# WX0_008_942DL.net
KiCad netlist of a schematic drawn in Altium Designer
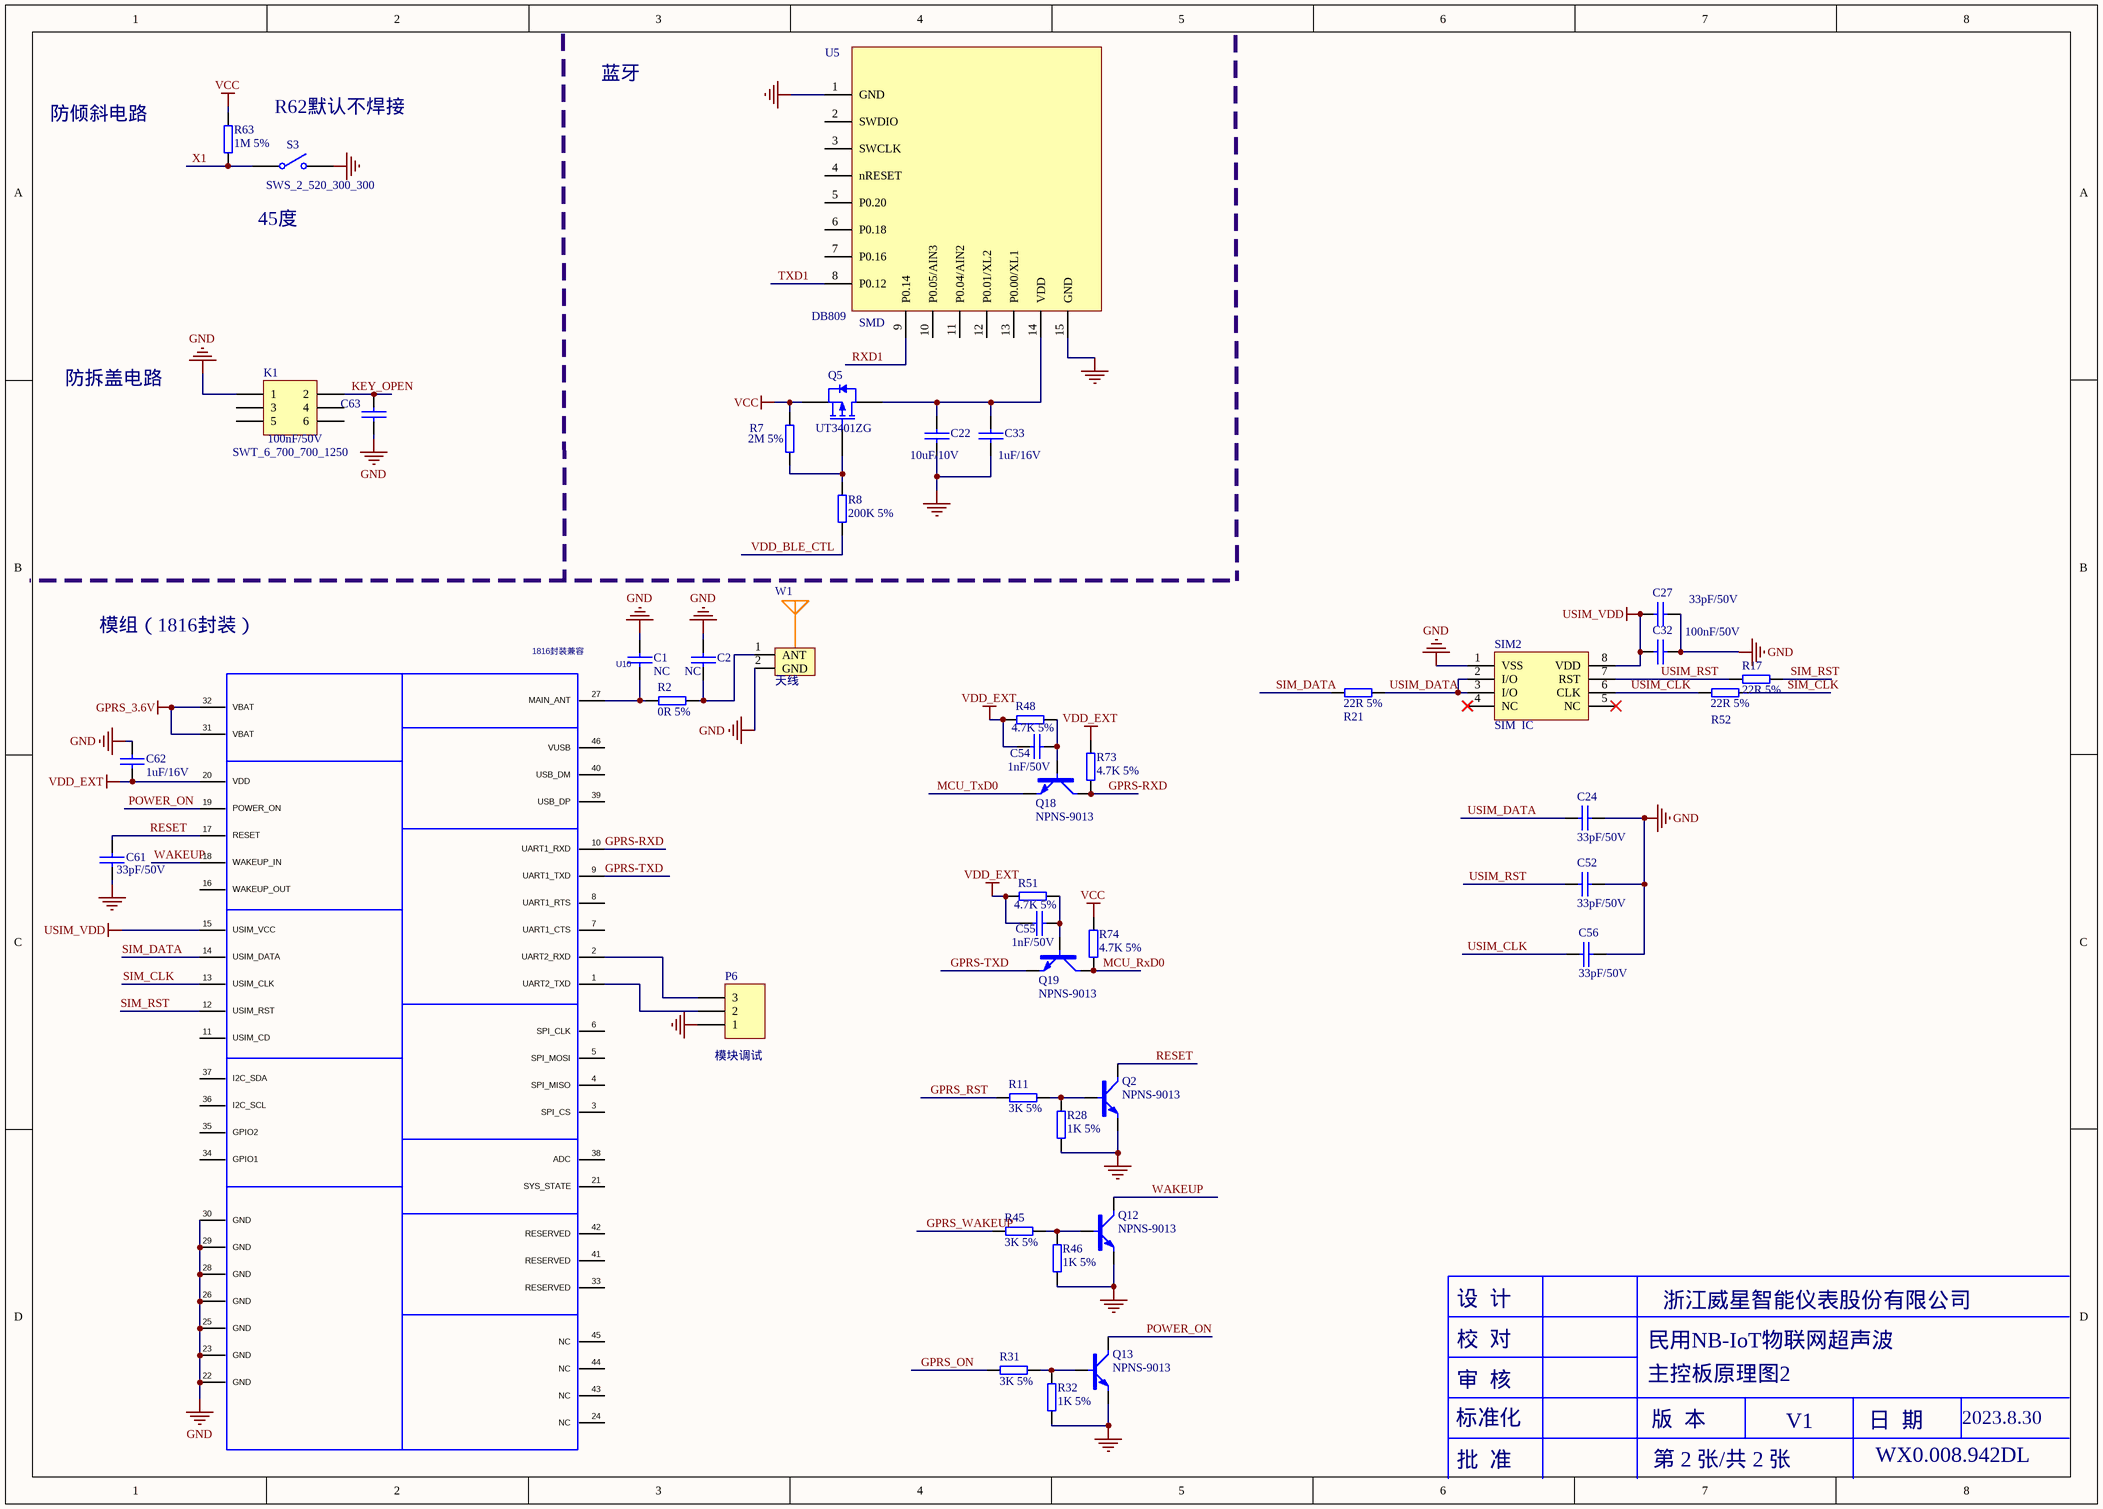
[diagram p0: WX0.008.942DL.SchDoc]

(export (version "E")
  (design (tool "Eeschema 10.0.6"))
  (components
    (comp (ref "C1")
      (value "NC")
      (footprint "CAP0603")
      (libsource (lib "Database_Libs2") (part "CC03JPO9_12P"))
    )
    (comp (ref "C2")
      (value "NC")
      (footprint "CAP0603")
      (libsource (lib "Database_Libs2") (part "CC03JPO9_12P"))
    )
    (comp (ref "C22")
      (value "10uF/10V")
      (footprint "CAP0603")
      (description "106pF,10 V,±10%,0603,村田,GRM188R61A106KE47D")
      (fields (field (name "PART NUMBER") "101020103-0026"))
      (libsource (lib "Database_Libs2") (part "CC03K5R6_10U"))
    )
    (comp (ref "C24")
      (value "33pF/50V")
      (footprint "CAP0603")
      (description "33pF,50 V,±10%,0603,国巨,CC0603KRNPO9BN33")
      (fields (field (name "PART NUMBER") "101020103-0027"))
      (libsource (lib "Database_Libs2") (part "CC03KPO9_33P"))
    )
    (comp (ref "C27")
      (value "33pF/50V")
      (footprint "CAP0603")
      (description "33pF,50 V,±10%,0603,国巨,CC0603KRNPO9BN33")
      (fields (field (name "PART NUMBER") "101020103-0027"))
      (libsource (lib "Database_Libs2") (part "CC03KPO9_33P"))
    )
    (comp (ref "C32")
      (value "100nF/50V")
      (footprint "CAP0603")
      (description "104pF,50 V,±10%,0603,国巨,CC0603KRX7R9BB104")
      (fields (field (name "PART NUMBER") "101020103-0021"))
      (libsource (lib "Database_Libs2") (part "CC03K7R9_100N"))
    )
    (comp (ref "C33")
      (value "1uF/16V")
      (footprint "CAP0603")
      (description "105pF,16 V,±10%,0603,国巨,CC0603KRX7R7BB105")
      (fields (field (name "PART NUMBER") "101020103-0003"))
      (libsource (lib "Database_Libs2") (part "CC03K7R7_1U"))
    )
    (comp (ref "C52")
      (value "33pF/50V")
      (footprint "CAP0603")
      (description "33pF,50 V,±10%,0603,国巨,CC0603KRNPO9BN33")
      (fields (field (name "PART NUMBER") "101020103-0027"))
      (libsource (lib "Database_Libs2") (part "CC03KPO9_33P"))
    )
    (comp (ref "C54")
      (value "1nF/50V")
      (footprint "CAP0603")
      (description "102pF,50 V,±10%,0603,国巨,CC0603KRX7R9BB102")
      (fields (field (name "PART NUMBER") "101020103-0022"))
      (libsource (lib "Database_Libs1") (part "CC03K7R9_1N"))
    )
    (comp (ref "C55")
      (value "1nF/50V")
      (footprint "CAP0603")
      (description "102pF,50 V,±10%,0603,国巨,CC0603KRX7R9BB102")
      (fields (field (name "PART NUMBER") "101020103-0022"))
      (libsource (lib "Database_Libs1") (part "CC03K7R9_1N"))
    )
    (comp (ref "C56")
      (value "33pF/50V")
      (footprint "CAP0603")
      (description "33pF,50 V,±10%,0603,国巨,CC0603KRNPO9BN33")
      (fields (field (name "PART NUMBER") "101020103-0027"))
      (libsource (lib "Database_Libs2") (part "CC03KPO9_33P"))
    )
    (comp (ref "C61")
      (value "33pF/50V")
      (footprint "CAP0603")
      (description "33pF,50 V,±10%,0603,国巨,CC0603KRNPO9BN33")
      (fields (field (name "PART NUMBER") "101020103-0027"))
      (libsource (lib "Database_Libs2") (part "CC03KPO9_33P"))
    )
    (comp (ref "C62")
      (value "1uF/16V")
      (footprint "CAP0603")
      (description "105pF,16 V,±10%,0603,国巨,CC0603KRX7R7BB105")
      (fields (field (name "PART NUMBER") "101020103-0003"))
      (libsource (lib "Database_Libs1") (part "CC03K7R7_1U"))
    )
    (comp (ref "C63")
      (value "100nF/50V")
      (footprint "CAP0603")
      (description "104pF,50 V,±10%,0603,国巨,CC0603KRX7R9BB104")
      (fields (field (name "PART NUMBER") "101020103-0021"))
      (libsource (lib "Database_Libs2") (part "CC03K7R9_100N"))
    )
    (comp (ref "K1")
      (value "SWT_6_700_700_1250")
      (footprint "KFT DIP-5.8X5.8")
      (description "7*7无锁按键,点触,7*7*12.5mm,7*7无锁按键,正立")
      (fields (field (name "PART NUMBER") "1011001-0037"))
      (libsource (lib "Database_Libs2") (part "07_SWT_6_700_700_1250"))
    )
    (comp (ref "P6")
      (value "模块调试")
      (footprint "PIN254_1*3*WXHJ")
      (description "1*3 ，Φ1.0 ，2.54mm，直脚,无需焊接器件")
      (fields (field (name "PART NUMBER") "AD_WXHJ_PinHeader_04"))
      (libsource (lib "Database_Libs2") (part "PIN254_1*3*WXHJ"))
    )
    (comp (ref "Q2")
      (value "NPNS-9013")
      (footprint "SOT-23")
      (description "9013,NPN,SOT-23,长电,S9013")
      (fields (field (name "PART NUMBER") "101040201-0002"))
      (libsource (lib "Database_Libs2") (part "03_NPNS-9013"))
    )
    (comp (ref "Q5")
      (value "UT3401ZG")
      (footprint "SOT-23")
      (description "UT3401ZG,P-MOS,SOT-23,UTC,UT3401ZG")
      (fields (field (name "PART NUMBER") "101040201-0013"))
      (libsource (lib "Database_Libs2") (part "03_P-UT3401ZG"))
    )
    (comp (ref "Q12")
      (value "NPNS-9013")
      (footprint "SOT-23")
      (description "9013,NPN,SOT-23,长电,S9013")
      (fields (field (name "PART NUMBER") "101040201-0002"))
      (libsource (lib "Database_Libs2") (part "03_NPNS-9013"))
    )
    (comp (ref "Q13")
      (value "NPNS-9013")
      (footprint "SOT-23")
      (description "9013,NPN,SOT-23,长电,S9013")
      (fields (field (name "PART NUMBER") "101040201-0002"))
      (libsource (lib "Database_Libs2") (part "03_NPNS-9013"))
    )
    (comp (ref "Q18")
      (value "NPNS-9013")
      (footprint "SOT-23")
      (description "9013,NPN,SOT-23,长电,S9013")
      (fields (field (name "PART NUMBER") "101040201-0002"))
      (libsource (lib "Database_Libs1") (part "03_NPNS-9013"))
    )
    (comp (ref "Q19")
      (value "NPNS-9013")
      (footprint "SOT-23")
      (description "9013,NPN,SOT-23,长电,S9013")
      (fields (field (name "PART NUMBER") "101040201-0002"))
      (libsource (lib "Database_Libs1") (part "03_NPNS-9013"))
    )
    (comp (ref "R2")
      (value "0R 5%")
      (footprint "RES0603")
      (description "国巨,±5%,0603,,155 ℃,-55 ℃,RC0603J2-070RL,无铅,200 ppm/℃,1/10W,,0R")
      (fields (field (name "PART NUMBER") "101010103-0001"))
      (libsource (lib "Database_Libs2") (part "RC03J_0R"))
    )
    (comp (ref "R7")
      (value "2M 5%")
      (footprint "RES0603")
      (description "国巨,±5%,0603,,155 ℃,-55 ℃,RC0603JR-072ML,含铅,100 ppm/℃,1/10W,,2M")
      (fields (field (name "PART NUMBER") "101010103-0025"))
      (libsource (lib "Database_Libs2") (part "RC03J_2M"))
    )
    (comp (ref "R8")
      (value "200K 5%")
      (footprint "RES0603")
      (description "10K±5%,1/10W,0603")
      (fields (field (name "PART NUMBER") "101010103-0003"))
      (libsource (lib "Database_Libs1") (part "RC03JF_10K"))
    )
    (comp (ref "R11")
      (value "3K 5%")
      (footprint "RES0603")
      (description "国巨,±5%,0603,,155 ℃,-55 ℃,RC0603JR-073KL,无铅,100 ppm/℃,1/10W,,3K")
      (fields (field (name "PART NUMBER") "101010103-0006"))
      (libsource (lib "Database_Libs2") (part "RC03J_3K"))
    )
    (comp (ref "R17")
      (value "22R 5%")
      (footprint "RES0603")
      (description "国巨,±5%,0603,,155 ℃,-55 ℃,RC0603JR-0722RL,无铅,200 ppm/℃,1/10W,,22欧")
      (fields (field (name "PART NUMBER") "101010103-0009"))
      (libsource (lib "Database_Libs2") (part "RC03J_22R"))
    )
    (comp (ref "R21")
      (value "22R 5%")
      (footprint "RES0603")
      (description "国巨,±5%,0603,,155 ℃,-55 ℃,RC0603JR-0722RL,无铅,200 ppm/℃,1/10W,,22欧")
      (fields (field (name "PART NUMBER") "101010103-0009"))
      (libsource (lib "Database_Libs2") (part "RC03J_22R"))
    )
    (comp (ref "R28")
      (value "1K 5%")
      (footprint "RES0603")
      (description "1K,±5%,1/10W,0603,国巨,RC0603JR-071KL")
      (fields (field (name "PART NUMBER") "101010103-0008"))
      (libsource (lib "Database_Libs2") (part "RC03J_1K"))
    )
    (comp (ref "R31")
      (value "3K 5%")
      (footprint "RES0603")
      (description "国巨,±5%,0603,,155 ℃,-55 ℃,RC0603JR-073KL,无铅,100 ppm/℃,1/10W,,3K")
      (fields (field (name "PART NUMBER") "101010103-0006"))
      (libsource (lib "Database_Libs2") (part "RC03J_3K"))
    )
    (comp (ref "R32")
      (value "1K 5%")
      (footprint "RES0603")
      (description "1K,±5%,1/10W,0603,国巨,RC0603JR-071KL")
      (fields (field (name "PART NUMBER") "101010103-0008"))
      (libsource (lib "Database_Libs2") (part "RC03J_1K"))
    )
    (comp (ref "R45")
      (value "3K 5%")
      (footprint "RES0603")
      (description "国巨,±5%,0603,,155 ℃,-55 ℃,RC0603JR-073KL,无铅,100 ppm/℃,1/10W,,3K")
      (fields (field (name "PART NUMBER") "101010103-0006"))
      (libsource (lib "Database_Libs2") (part "RC03J_3K"))
    )
    (comp (ref "R46")
      (value "1K 5%")
      (footprint "RES0603")
      (description "1K,±5%,1/10W,0603,国巨,RC0603JR-071KL")
      (fields (field (name "PART NUMBER") "101010103-0008"))
      (libsource (lib "Database_Libs2") (part "RC03J_1K"))
    )
    (comp (ref "R48")
      (value "4.7K 5%")
      (footprint "RES0603")
      (description "4.7K±5%,1/10W,0603")
      (fields (field (name "PART NUMBER") "101010103-0042"))
      (libsource (lib "Database_Libs2") (part "RC03J_4.7K"))
    )
    (comp (ref "R51")
      (value "4.7K 5%")
      (footprint "RES0603")
      (description "4.7K±5%,1/10W,0603")
      (fields (field (name "PART NUMBER") "101010103-0042"))
      (libsource (lib "Database_Libs2") (part "RC03J_4.7K"))
    )
    (comp (ref "R52")
      (value "22R 5%")
      (footprint "RES0603")
      (description "国巨,±5%,0603,,155 ℃,-55 ℃,RC0603JR-0722RL,无铅,200 ppm/℃,1/10W,,22欧")
      (fields (field (name "PART NUMBER") "101010103-0009"))
      (libsource (lib "Database_Libs2") (part "RC03J_22R"))
    )
    (comp (ref "R63")
      (value "1M 5%")
      (footprint "RES0603")
      (description "国巨,±5%,0603,,155 ℃,-55 ℃,RC0603JR-071ML,无铅,200 ppm/℃,1/10W,,1M")
      (fields (field (name "PART NUMBER") "101010103-0002"))
      (libsource (lib "Database_Libs2") (part "RC03J_1M"))
    )
    (comp (ref "R73")
      (value "4.7K 5%")
      (footprint "RES0603")
      (description "4.7K±5%,1/10W,0603")
      (fields (field (name "PART NUMBER") "101010103-0042"))
      (libsource (lib "Database_Libs2") (part "RC03J_4.7K"))
    )
    (comp (ref "R74")
      (value "4.7K 5%")
      (footprint "RES0603")
      (description "4.7K±5%,1/10W,0603")
      (fields (field (name "PART NUMBER") "101010103-0042"))
      (libsource (lib "Database_Libs2") (part "RC03J_4.7K"))
    )
    (comp (ref "S3")
      (value "SWS_2_520_300_300")
      (footprint "SWS_2_520_300")
      (description "CSX-SEN-645B,垂直45°开关转换,3*5.2mm,360°任意方位倾斜检测,深圳市成晟科技有限公司")
      (fields (field (name "PART NUMBER") "1011001-0051"))
      (libsource (lib "Database_Libs2") (part "07_SWS_2_520_300_300"))
    )
    (comp (ref "SIM2")
      (value "SIM  IC")
      (footprint "SIMIC")
      (libsource (lib "PCB_Project") (part "SIMCARD_1"))
    )
    (comp (ref "U5")
      (value "DB809")
      (footprint "DB809")
      (description "北高智蓝牙模块DB809")
      (fields (field (name "PART NUMBER") "1011402-0194") (field (name "SMD/DIP") "SMD"))
      (libsource (lib "Database_Libs2") (part "01_DB809"))
    )
    (comp (ref "U10")
      (value "1816封装兼容")
      (footprint "N700-FIXTURE_DL_CFT_CQA")
      (description "N700-58-01,N700-58-01,通信模块,18.0mm*16.0mm*2.1mm,Band 5:850MHz/Band 8:900MHz,深圳市广和通无线股份有限公司")
      (fields (field (name "PART NUMBER") "1011402-0183"))
      (libsource (lib "Database_Libs2") (part "01_N700_CON_46"))
    )
    (comp (ref "W1")
      (value "天线")
      (footprint "ANT-IPEX_1")
      (description "UB06000058A,3*3.1*1.25mm,公头,单排,IPEX一代板端")
      (fields (field (name "PART NUMBER") "1010902-0145"))
      (libsource (lib "Database_Libs2") (part "天线"))
    )
  )
  (nets
    (net (code "1") (name "/GPRS-RXD") (class "Default")
      (node (ref "Q18") (pin "3") (pinfunction "C_3") (pintype "passive"))
      (node (ref "R73") (pin "1") (pinfunction "1_1") (pintype "passive"))
      (node (ref "U10") (pin "10") (pinfunction "UART1_RXD_10") (pintype "passive"))
    )
    (net (code "2") (name "/GPRS-TXD") (class "Default")
      (node (ref "Q19") (pin "2") (pinfunction "E_2") (pintype "passive"))
      (node (ref "U10") (pin "9") (pinfunction "UART1_TXD_9") (pintype "passive"))
    )
    (net (code "3") (name "/GPRS_ON") (class "Default")
      (node (ref "R31") (pin "1") (pinfunction "1_1") (pintype "passive"))
    )
    (net (code "4") (name "/GPRS_RST") (class "Default")
      (node (ref "R11") (pin "1") (pinfunction "1_1") (pintype "passive"))
    )
    (net (code "5") (name "/GPRS_WAKEUP") (class "Default")
      (node (ref "R45") (pin "1") (pinfunction "1_1") (pintype "passive"))
    )
    (net (code "6") (name "/KEY_OPEN") (class "Default")
      (node (ref "C63") (pin "2") (pinfunction "2_2") (pintype "passive"))
      (node (ref "K1") (pin "2") (pinfunction "2_2") (pintype "passive"))
    )
    (net (code "7") (name "/MCU_RxD0") (class "Default")
      (node (ref "Q19") (pin "3") (pinfunction "C_3") (pintype "passive"))
      (node (ref "R74") (pin "1") (pinfunction "1_1") (pintype "passive"))
    )
    (net (code "8") (name "/MCU_TxD0") (class "Default")
      (node (ref "Q18") (pin "2") (pinfunction "E_2") (pintype "passive"))
    )
    (net (code "9") (name "/POWER_ON") (class "Default")
      (node (ref "Q13") (pin "3") (pinfunction "C_3") (pintype "passive"))
      (node (ref "U10") (pin "19") (pinfunction "POWER_ON_19") (pintype "passive"))
    )
    (net (code "10") (name "/RESET") (class "Default")
      (node (ref "C61") (pin "2") (pinfunction "2_2") (pintype "passive"))
      (node (ref "Q2") (pin "3") (pinfunction "C_3") (pintype "passive"))
      (node (ref "U10") (pin "17") (pinfunction "RESET_17") (pintype "passive"))
    )
    (net (code "11") (name "/RXD1") (class "Default")
      (node (ref "U5") (pin "9") (pinfunction "P0.14_9") (pintype "passive"))
    )
    (net (code "12") (name "/SIM_CLK") (class "Default")
      (node (ref "R52") (pin "2") (pinfunction "2_2") (pintype "passive"))
      (node (ref "U10") (pin "13") (pinfunction "USIM_CLK_13") (pintype "passive"))
    )
    (net (code "13") (name "/SIM_DATA") (class "Default")
      (node (ref "R21") (pin "1") (pinfunction "1_1") (pintype "passive"))
      (node (ref "U10") (pin "14") (pinfunction "USIM_DATA_14") (pintype "passive"))
    )
    (net (code "14") (name "/SIM_RST") (class "Default")
      (node (ref "R17") (pin "2") (pinfunction "2_2") (pintype "passive"))
      (node (ref "U10") (pin "12") (pinfunction "USIM_RST_12") (pintype "passive"))
    )
    (net (code "15") (name "/TXD1") (class "Default")
      (node (ref "U5") (pin "8") (pinfunction "P0.12_8") (pintype "passive"))
    )
    (net (code "16") (name "/USIM_CLK") (class "Default")
      (node (ref "C56") (pin "2") (pinfunction "2_2") (pintype "passive"))
      (node (ref "R52") (pin "1") (pinfunction "1_1") (pintype "passive"))
      (node (ref "SIM2") (pin "6") (pinfunction "CLK_6") (pintype "passive"))
    )
    (net (code "17") (name "/USIM_DATA") (class "Default")
      (node (ref "C24") (pin "2") (pinfunction "2_2") (pintype "passive"))
      (node (ref "R21") (pin "2") (pinfunction "2_2") (pintype "passive"))
      (node (ref "SIM2") (pin "2") (pinfunction "I/O_2") (pintype "passive"))
      (node (ref "SIM2") (pin "3") (pinfunction "I/O_3") (pintype "passive"))
    )
    (net (code "18") (name "/USIM_RST") (class "Default")
      (node (ref "C52") (pin "2") (pinfunction "2_2") (pintype "passive"))
      (node (ref "R17") (pin "1") (pinfunction "1_1") (pintype "passive"))
      (node (ref "SIM2") (pin "7") (pinfunction "RST_7") (pintype "passive"))
    )
    (net (code "19") (name "/VDD_BLE_CTL") (class "Default")
      (node (ref "R8") (pin "1") (pinfunction "1_1") (pintype "passive"))
    )
    (net (code "20") (name "/WAKEUP") (class "Default")
      (node (ref "Q12") (pin "3") (pinfunction "C_3") (pintype "passive"))
      (node (ref "U10") (pin "18") (pinfunction "WAKEUP_IN_18") (pintype "passive"))
    )
    (net (code "21") (name "/X1") (class "Default")
      (node (ref "R63") (pin "1") (pinfunction "1_1") (pintype "passive"))
      (node (ref "S3") (pin "1") (pintype "passive"))
    )
    (net (code "22") (name "GND") (class "Default")
      (node (ref "C1") (pin "2") (pinfunction "2_2") (pintype "passive"))
      (node (ref "C2") (pin "2") (pinfunction "2_2") (pintype "passive"))
      (node (ref "C22") (pin "2") (pinfunction "2_2") (pintype "passive"))
      (node (ref "C24") (pin "1") (pinfunction "1_1") (pintype "passive"))
      (node (ref "C27") (pin "1") (pinfunction "1_1") (pintype "passive"))
      (node (ref "C32") (pin "2") (pinfunction "2_2") (pintype "passive"))
      (node (ref "C33") (pin "2") (pinfunction "2_2") (pintype "passive"))
      (node (ref "C52") (pin "1") (pinfunction "1_1") (pintype "passive"))
      (node (ref "C56") (pin "1") (pinfunction "1_1") (pintype "passive"))
      (node (ref "C61") (pin "1") (pinfunction "1_1") (pintype "passive"))
      (node (ref "C62") (pin "2") (pinfunction "2_2") (pintype "passive"))
      (node (ref "C63") (pin "1") (pinfunction "1_1") (pintype "passive"))
      (node (ref "K1") (pin "1") (pinfunction "1_1") (pintype "passive"))
      (node (ref "P6") (pin "1") (pinfunction "1_1") (pintype "passive"))
      (node (ref "Q12") (pin "2") (pinfunction "E_2") (pintype "passive"))
      (node (ref "Q13") (pin "2") (pinfunction "E_2") (pintype "passive"))
      (node (ref "Q2") (pin "2") (pinfunction "E_2") (pintype "passive"))
      (node (ref "R28") (pin "1") (pinfunction "1_1") (pintype "passive"))
      (node (ref "R32") (pin "1") (pinfunction "1_1") (pintype "passive"))
      (node (ref "R46") (pin "1") (pinfunction "1_1") (pintype "passive"))
      (node (ref "S3") (pin "2") (pintype "passive"))
      (node (ref "SIM2") (pin "1") (pinfunction "VSS_1") (pintype "passive"))
      (node (ref "U10") (pin "22") (pinfunction "GND_22") (pintype "passive"))
      (node (ref "U10") (pin "23") (pinfunction "GND_23") (pintype "passive"))
      (node (ref "U10") (pin "25") (pinfunction "GND_25") (pintype "passive"))
      (node (ref "U10") (pin "26") (pinfunction "GND_26") (pintype "passive"))
      (node (ref "U10") (pin "28") (pinfunction "GND_28") (pintype "passive"))
      (node (ref "U10") (pin "29") (pinfunction "GND_29") (pintype "passive"))
      (node (ref "U10") (pin "30") (pinfunction "GND_30") (pintype "passive"))
      (node (ref "U5") (pin "1") (pinfunction "GND_1") (pintype "passive"))
      (node (ref "U5") (pin "15") (pinfunction "GND_15") (pintype "passive"))
      (node (ref "W1") (pin "2") (pinfunction "GND_2") (pintype "passive"))
    )
    (net (code "23") (name "GPRS_3.6V") (class "Default")
      (node (ref "U10") (pin "31") (pinfunction "VBAT_31") (pintype "passive"))
      (node (ref "U10") (pin "32") (pinfunction "VBAT_32") (pintype "passive"))
    )
    (net (code "24") (name "Net-(Q2-B)") (class "Default")
      (node (ref "Q2") (pin "1") (pinfunction "B_1") (pintype "passive"))
      (node (ref "R11") (pin "2") (pinfunction "2_2") (pintype "passive"))
      (node (ref "R28") (pin "2") (pinfunction "2_2") (pintype "passive"))
    )
    (net (code "25") (name "Net-(Q5-D)") (class "Default")
      (node (ref "C22") (pin "1") (pinfunction "1_1") (pintype "passive"))
      (node (ref "C33") (pin "1") (pinfunction "1_1") (pintype "passive"))
      (node (ref "Q5") (pin "3") (pinfunction "D_3") (pintype "passive"))
      (node (ref "U5") (pin "14") (pinfunction "VDD_14") (pintype "passive"))
    )
    (net (code "26") (name "Net-(Q5-G)") (class "Default")
      (node (ref "Q5") (pin "1") (pinfunction "G_1") (pintype "passive"))
      (node (ref "R7") (pin "1") (pinfunction "1_1") (pintype "passive"))
      (node (ref "R8") (pin "2") (pinfunction "2_2") (pintype "passive"))
    )
    (net (code "27") (name "Net-(Q12-B)") (class "Default")
      (node (ref "Q12") (pin "1") (pinfunction "B_1") (pintype "passive"))
      (node (ref "R45") (pin "2") (pinfunction "2_2") (pintype "passive"))
      (node (ref "R46") (pin "2") (pinfunction "2_2") (pintype "passive"))
    )
    (net (code "28") (name "Net-(Q13-B)") (class "Default")
      (node (ref "Q13") (pin "1") (pinfunction "B_1") (pintype "passive"))
      (node (ref "R31") (pin "2") (pinfunction "2_2") (pintype "passive"))
      (node (ref "R32") (pin "2") (pinfunction "2_2") (pintype "passive"))
    )
    (net (code "29") (name "Net-(Q18-B)") (class "Default")
      (node (ref "C54") (pin "2") (pinfunction "2_2") (pintype "passive"))
      (node (ref "Q18") (pin "1") (pinfunction "B_1") (pintype "passive"))
      (node (ref "R48") (pin "1") (pinfunction "1_1") (pintype "passive"))
    )
    (net (code "30") (name "Net-(Q19-B)") (class "Default")
      (node (ref "C55") (pin "2") (pinfunction "2_2") (pintype "passive"))
      (node (ref "Q19") (pin "1") (pinfunction "B_1") (pintype "passive"))
      (node (ref "R51") (pin "1") (pinfunction "1_1") (pintype "passive"))
    )
    (net (code "31") (name "Net-(U10-MAIN_ANT)") (class "Default")
      (node (ref "C1") (pin "1") (pinfunction "1_1") (pintype "passive"))
      (node (ref "R2") (pin "2") (pinfunction "2_2") (pintype "passive"))
      (node (ref "U10") (pin "27") (pinfunction "MAIN_ANT_27") (pintype "passive"))
    )
    (net (code "32") (name "Net-(U10-UART2_RXD)") (class "Default")
      (node (ref "P6") (pin "3") (pinfunction "3_3") (pintype "passive"))
      (node (ref "U10") (pin "2") (pinfunction "UART2_RXD_2") (pintype "passive"))
    )
    (net (code "33") (name "Net-(U10-UART2_TXD)") (class "Default")
      (node (ref "P6") (pin "2") (pinfunction "2_2") (pintype "passive"))
      (node (ref "U10") (pin "1") (pinfunction "UART2_TXD_1") (pintype "passive"))
    )
    (net (code "34") (name "Net-(W1-ANT)") (class "Default")
      (node (ref "C2") (pin "1") (pinfunction "1_1") (pintype "passive"))
      (node (ref "R2") (pin "1") (pinfunction "1_1") (pintype "passive"))
      (node (ref "W1") (pin "1") (pinfunction "ANT_1") (pintype "passive"))
    )
    (net (code "35") (name "USIM_VDD") (class "Default")
      (node (ref "C27") (pin "2") (pinfunction "2_2") (pintype "passive"))
      (node (ref "C32") (pin "1") (pinfunction "1_1") (pintype "passive"))
      (node (ref "SIM2") (pin "8") (pinfunction "VDD_8") (pintype "passive"))
      (node (ref "U10") (pin "15") (pinfunction "USIM_VCC_15") (pintype "passive"))
    )
    (net (code "36") (name "VCC") (class "Default")
      (node (ref "Q5") (pin "2") (pinfunction "S_2") (pintype "passive"))
      (node (ref "R63") (pin "2") (pinfunction "2_2") (pintype "passive"))
      (node (ref "R7") (pin "2") (pinfunction "2_2") (pintype "passive"))
      (node (ref "R74") (pin "2") (pinfunction "2_2") (pintype "passive"))
    )
    (net (code "37") (name "VDD_EXT") (class "Default")
      (node (ref "C54") (pin "1") (pinfunction "1_1") (pintype "passive"))
      (node (ref "C55") (pin "1") (pinfunction "1_1") (pintype "passive"))
      (node (ref "C62") (pin "1") (pinfunction "1_1") (pintype "passive"))
      (node (ref "R48") (pin "2") (pinfunction "2_2") (pintype "passive"))
      (node (ref "R51") (pin "2") (pinfunction "2_2") (pintype "passive"))
      (node (ref "R73") (pin "2") (pinfunction "2_2") (pintype "passive"))
      (node (ref "U10") (pin "20") (pinfunction "VDD_20") (pintype "passive"))
    )
    (net (code "38") (name "unconnected-(K1-Pad3)") (class "Default")
      (node (ref "K1") (pin "3") (pinfunction "3_3") (pintype "passive"))
    )
    (net (code "39") (name "unconnected-(K1-Pad4)") (class "Default")
      (node (ref "K1") (pin "4") (pinfunction "4_4") (pintype "passive"))
    )
    (net (code "40") (name "unconnected-(K1-Pad5)") (class "Default")
      (node (ref "K1") (pin "5") (pinfunction "5_5") (pintype "passive"))
    )
    (net (code "41") (name "unconnected-(K1-Pad6)") (class "Default")
      (node (ref "K1") (pin "6") (pinfunction "6_6") (pintype "passive"))
    )
    (net (code "42") (name "unconnected-(SIM2-NC-Pad4)") (class "Default")
      (node (ref "SIM2") (pin "4") (pinfunction "NC_4") (pintype "passive+no_connect"))
    )
    (net (code "43") (name "unconnected-(SIM2-NC-Pad5)") (class "Default")
      (node (ref "SIM2") (pin "5") (pinfunction "NC_5") (pintype "passive+no_connect"))
    )
    (net (code "44") (name "unconnected-(U5-P0.00{slash}XL1-Pad13)") (class "Default")
      (node (ref "U5") (pin "13") (pinfunction "P0.00/XL1_13") (pintype "passive"))
    )
    (net (code "45") (name "unconnected-(U5-P0.01{slash}XL2-Pad12)") (class "Default")
      (node (ref "U5") (pin "12") (pinfunction "P0.01/XL2_12") (pintype "passive"))
    )
    (net (code "46") (name "unconnected-(U5-P0.04{slash}AIN2-Pad11)") (class "Default")
      (node (ref "U5") (pin "11") (pinfunction "P0.04/AIN2_11") (pintype "passive"))
    )
    (net (code "47") (name "unconnected-(U5-P0.05{slash}AIN3-Pad10)") (class "Default")
      (node (ref "U5") (pin "10") (pinfunction "P0.05/AIN3_10") (pintype "passive"))
    )
    (net (code "48") (name "unconnected-(U5-P0.16-Pad7)") (class "Default")
      (node (ref "U5") (pin "7") (pinfunction "P0.16_7") (pintype "passive"))
    )
    (net (code "49") (name "unconnected-(U5-P0.18-Pad6)") (class "Default")
      (node (ref "U5") (pin "6") (pinfunction "P0.18_6") (pintype "passive"))
    )
    (net (code "50") (name "unconnected-(U5-P0.20-Pad5)") (class "Default")
      (node (ref "U5") (pin "5") (pinfunction "P0.20_5") (pintype "passive"))
    )
    (net (code "51") (name "unconnected-(U5-SWCLK-Pad3)") (class "Default")
      (node (ref "U5") (pin "3") (pinfunction "SWCLK_3") (pintype "passive"))
    )
    (net (code "52") (name "unconnected-(U5-SWDIO-Pad2)") (class "Default")
      (node (ref "U5") (pin "2") (pinfunction "SWDIO_2") (pintype "passive"))
    )
    (net (code "53") (name "unconnected-(U5-nRESET-Pad4)") (class "Default")
      (node (ref "U5") (pin "4") (pinfunction "nRESET_4") (pintype "passive"))
    )
    (net (code "54") (name "unconnected-(U10-ADC-Pad38)") (class "Default")
      (node (ref "U10") (pin "38") (pinfunction "ADC_38") (pintype "passive"))
    )
    (net (code "55") (name "unconnected-(U10-GPIO1-Pad34)") (class "Default")
      (node (ref "U10") (pin "34") (pinfunction "GPIO1_34") (pintype "passive"))
    )
    (net (code "56") (name "unconnected-(U10-GPIO2-Pad35)") (class "Default")
      (node (ref "U10") (pin "35") (pinfunction "GPIO2_35") (pintype "passive"))
    )
    (net (code "57") (name "unconnected-(U10-I2C_SCL-Pad36)") (class "Default")
      (node (ref "U10") (pin "36") (pinfunction "I2C_SCL_36") (pintype "passive"))
    )
    (net (code "58") (name "unconnected-(U10-I2C_SDA-Pad37)") (class "Default")
      (node (ref "U10") (pin "37") (pinfunction "I2C_SDA_37") (pintype "passive"))
    )
    (net (code "59") (name "unconnected-(U10-NC-Pad24)") (class "Default")
      (node (ref "U10") (pin "24") (pinfunction "NC_24") (pintype "passive"))
    )
    (net (code "60") (name "unconnected-(U10-NC-Pad43)") (class "Default")
      (node (ref "U10") (pin "43") (pinfunction "NC_43") (pintype "passive"))
    )
    (net (code "61") (name "unconnected-(U10-NC-Pad44)") (class "Default")
      (node (ref "U10") (pin "44") (pinfunction "NC_44") (pintype "passive"))
    )
    (net (code "62") (name "unconnected-(U10-NC-Pad45)") (class "Default")
      (node (ref "U10") (pin "45") (pinfunction "NC_45") (pintype "passive"))
    )
    (net (code "63") (name "unconnected-(U10-RESERVED-Pad33)") (class "Default")
      (node (ref "U10") (pin "33") (pinfunction "RESERVED_33") (pintype "passive"))
    )
    (net (code "64") (name "unconnected-(U10-RESERVED-Pad41)") (class "Default")
      (node (ref "U10") (pin "41") (pinfunction "RESERVED_41") (pintype "passive"))
    )
    (net (code "65") (name "unconnected-(U10-RESERVED-Pad42)") (class "Default")
      (node (ref "U10") (pin "42") (pinfunction "RESERVED_42") (pintype "passive"))
    )
    (net (code "66") (name "unconnected-(U10-SPI_CLK-Pad6)") (class "Default")
      (node (ref "U10") (pin "6") (pinfunction "SPI_CLK_6") (pintype "passive"))
    )
    (net (code "67") (name "unconnected-(U10-SPI_CS-Pad3)") (class "Default")
      (node (ref "U10") (pin "3") (pinfunction "SPI_CS_3") (pintype "passive"))
    )
    (net (code "68") (name "unconnected-(U10-SPI_MISO-Pad4)") (class "Default")
      (node (ref "U10") (pin "4") (pinfunction "SPI_MISO_4") (pintype "passive"))
    )
    (net (code "69") (name "unconnected-(U10-SPI_MOSI-Pad5)") (class "Default")
      (node (ref "U10") (pin "5") (pinfunction "SPI_MOSI_5") (pintype "passive"))
    )
    (net (code "70") (name "unconnected-(U10-SYS_STATE-Pad21)") (class "Default")
      (node (ref "U10") (pin "21") (pinfunction "SYS_STATE_21") (pintype "passive"))
    )
    (net (code "71") (name "unconnected-(U10-UART1_CTS-Pad7)") (class "Default")
      (node (ref "U10") (pin "7") (pinfunction "UART1_CTS_7") (pintype "passive"))
    )
    (net (code "72") (name "unconnected-(U10-UART1_RTS-Pad8)") (class "Default")
      (node (ref "U10") (pin "8") (pinfunction "UART1_RTS_8") (pintype "passive"))
    )
    (net (code "73") (name "unconnected-(U10-USB_DM-Pad40)") (class "Default")
      (node (ref "U10") (pin "40") (pinfunction "USB_DM_40") (pintype "passive"))
    )
    (net (code "74") (name "unconnected-(U10-USB_DP-Pad39)") (class "Default")
      (node (ref "U10") (pin "39") (pinfunction "USB_DP_39") (pintype "passive"))
    )
    (net (code "75") (name "unconnected-(U10-USIM_CD-Pad11)") (class "Default")
      (node (ref "U10") (pin "11") (pinfunction "USIM_CD_11") (pintype "passive"))
    )
    (net (code "76") (name "unconnected-(U10-VUSB-Pad46)") (class "Default")
      (node (ref "U10") (pin "46") (pinfunction "VUSB_46") (pintype "passive"))
    )
    (net (code "77") (name "unconnected-(U10-WAKEUP_OUT-Pad16)") (class "Default")
      (node (ref "U10") (pin "16") (pinfunction "WAKEUP_OUT_16") (pintype "passive"))
    )
  )
)
